# AS5157.net
KiCad netlist of a schematic drawn in EAGLE
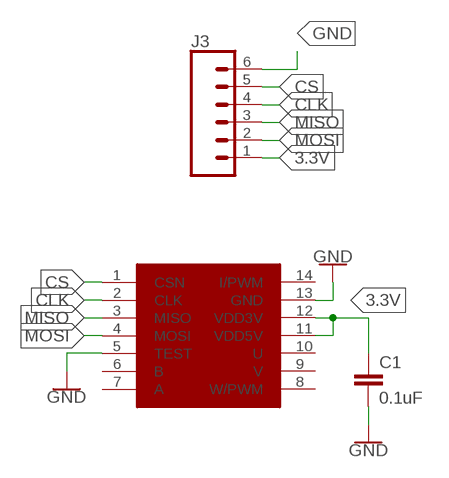
[diagram p0: schematic, sheet 1]

(export (version "E")
  (design (tool "Eeschema 10.0.6"))
  (components
    (comp (ref "C1")
      (value "0.1uF")
      (footprint "eagle-import:0603")
      (libsource (lib "eagle-import") (part "0.1UF-0603-25V-5%"))
    )
    (comp (ref "J3")
      (value "CONN_06SMD-1MM")
      (footprint "eagle-import:1X06-1MM")
      (libsource (lib "eagle-import") (part "CONN_06SMD-1MM"))
    )
    (comp (ref "U$1")
      (value "AS5147")
      (footprint "eagle-import:TSSOP14")
      (libsource (lib "eagle-import") (part "AS5147"))
    )
  )
  (nets
    (net (code "1") (name "3.3V") (class "Default")
      (node (ref "C1") (pin "1") (pinfunction "1_1") (pintype "passive"))
      (node (ref "J3") (pin "1") (pinfunction "1_1") (pintype "passive"))
      (node (ref "U$1") (pin "11") (pinfunction "VDD5V_11") (pintype "power_in"))
      (node (ref "U$1") (pin "12") (pinfunction "VDD3V_12") (pintype "power_in"))
    )
    (net (code "2") (name "CLK") (class "Default")
      (node (ref "J3") (pin "4") (pinfunction "4_4") (pintype "passive"))
      (node (ref "U$1") (pin "2") (pinfunction "CLK_2") (pintype "input"))
    )
    (net (code "3") (name "CS") (class "Default")
      (node (ref "J3") (pin "5") (pinfunction "5_5") (pintype "passive"))
      (node (ref "U$1") (pin "1") (pinfunction "CSN_1") (pintype "input"))
    )
    (net (code "4") (name "GND") (class "Default")
      (node (ref "C1") (pin "2") (pinfunction "2_2") (pintype "passive"))
      (node (ref "J3") (pin "6") (pinfunction "6_6") (pintype "passive"))
      (node (ref "U$1") (pin "13") (pinfunction "GND_13") (pintype "power_in"))
      (node (ref "U$1") (pin "5") (pinfunction "TEST_5") (pintype "input"))
    )
    (net (code "5") (name "MISO") (class "Default")
      (node (ref "J3") (pin "3") (pinfunction "3_3") (pintype "passive"))
      (node (ref "U$1") (pin "3") (pinfunction "MISO_3") (pintype "output"))
    )
    (net (code "6") (name "MOSI") (class "Default")
      (node (ref "J3") (pin "2") (pinfunction "2_2") (pintype "passive"))
      (node (ref "U$1") (pin "4") (pinfunction "MOSI_4") (pintype "input"))
    )
    (net (code "7") (name "unconnected-(U$1-A-Pad7)") (class "Default")
      (node (ref "U$1") (pin "7") (pinfunction "A_7") (pintype "output"))
    )
    (net (code "8") (name "unconnected-(U$1-B-Pad6)") (class "Default")
      (node (ref "U$1") (pin "6") (pinfunction "B_6") (pintype "output"))
    )
    (net (code "9") (name "unconnected-(U$1-I{slash}PWM-Pad14)") (class "Default")
      (node (ref "U$1") (pin "14") (pinfunction "I/PWM_14") (pintype "output"))
    )
    (net (code "10") (name "unconnected-(U$1-U-Pad10)") (class "Default")
      (node (ref "U$1") (pin "10") (pinfunction "U_10") (pintype "output"))
    )
    (net (code "11") (name "unconnected-(U$1-V-Pad9)") (class "Default")
      (node (ref "U$1") (pin "9") (pinfunction "V_9") (pintype "output"))
    )
    (net (code "12") (name "unconnected-(U$1-W{slash}PWM-Pad8)") (class "Default")
      (node (ref "U$1") (pin "8") (pinfunction "W/PWM_8") (pintype "output"))
    )
  )
)
